# POWER_NEGATIVE.net
KiCad netlist of a schematic drawn in Altium Designer
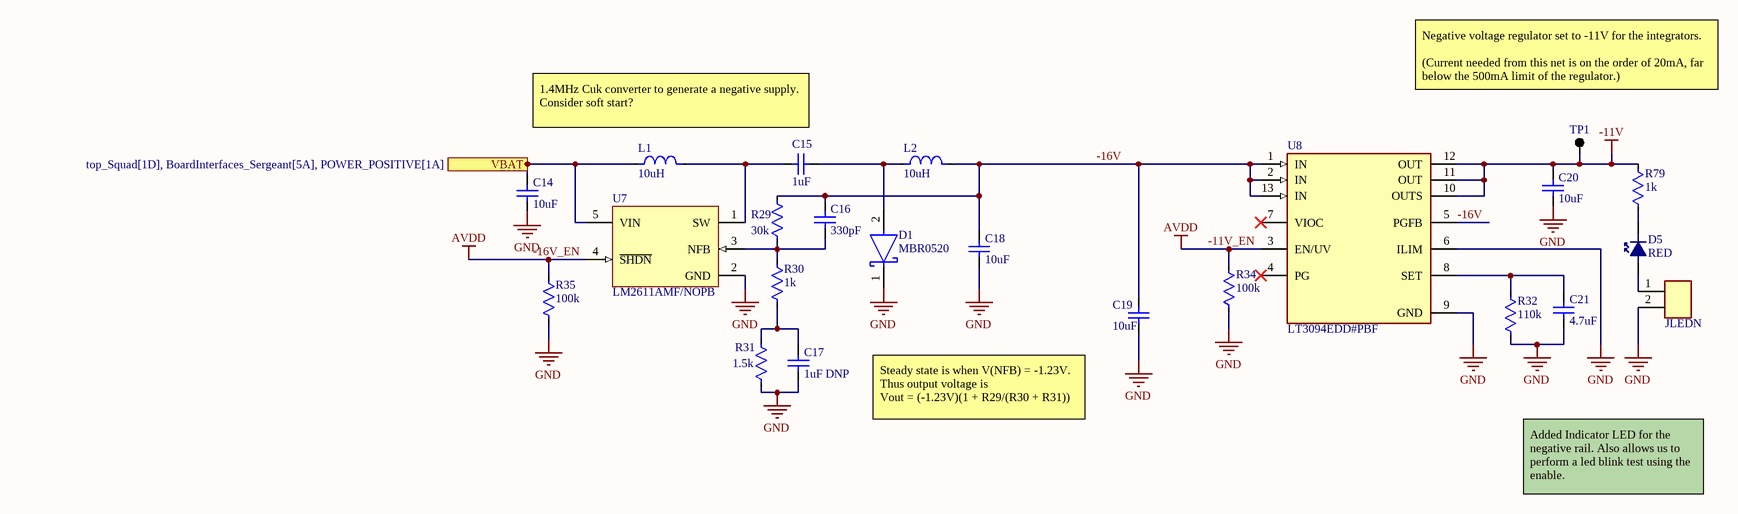
[diagram p0: POWER_NEGATIVE.SchDoc]

(export (version "E")
  (design (tool "Eeschema 10.0.6"))
  (components
    (comp (ref "C14")
      (value "10uF")
      (footprint "CAP 0805 IPC MID DENSITY")
      (description "Murata GRM21BR61E106KA73L - Cap Ceramic 10uF 10% 25V X5R 0805")
      (fields (field (name "MF") "Murata") (field (name "MP") "GRM21BR61E106KA73L"))
      (libsource (lib "ALTAIR_PD_Capacitors") (part "CAP"))
    )
    (comp (ref "C15")
      (value "1uF")
      (footprint "CAP 0603 IPC MID DENSITY")
      (description "Murata GRT188R61H105KE13D - Cap MLCC AEC-Q200 X5R 1uF 50V 0603")
      (fields (field (name "MF") "Murata") (field (name "MP") "GRT188R61H105KE13D"))
      (libsource (lib "ALTAIR_PD_Capacitors") (part "CAP"))
    )
    (comp (ref "C16")
      (value "330pF")
      (footprint "CAP 1206 NON-IPC KEMET NP0")
      (description "Kemet C1206C331J5GACTU - Cap Ceramic 330pF 50V 5% NP0 1206")
      (fields (field (name "MF") "Kemet") (field (name "MP") "C1206C331J5GACTU"))
      (libsource (lib "ALTAIR_PD_Capacitors") (part "CAP"))
    )
    (comp (ref "C17")
      (value "1uF DNP")
      (footprint "CAP 0603 IPC MID DENSITY")
      (description "Murata GRT188R61H105KE13D - Cap MLCC AEC-Q200 X5R 1uF 50V 0603")
      (fields (field (name "MF") "Murata") (field (name "MP") "GRT188R61H105KE13D"))
      (libsource (lib "ALTAIR_PD_Capacitors") (part "CAP"))
    )
    (comp (ref "C18")
      (value "10uF")
      (footprint "CAP 0805 IPC MID DENSITY")
      (description "Murata GRM21BR61E106KA73L - Cap Ceramic 10uF 10% 25V X5R 0805")
      (fields (field (name "MF") "Murata") (field (name "MP") "GRM21BR61E106KA73L"))
      (libsource (lib "ALTAIR_PD_Capacitors") (part "CAP"))
    )
    (comp (ref "C19")
      (value "10uF")
      (footprint "CAP 0805 IPC MID DENSITY")
      (description "Murata GRM21BR61E106KA73L - Cap Ceramic 10uF 10% 25V X5R 0805")
      (fields (field (name "MF") "Murata") (field (name "MP") "GRM21BR61E106KA73L"))
      (libsource (lib "ALTAIR_PD_Capacitors") (part "CAP"))
    )
    (comp (ref "C20")
      (value "10uF")
      (footprint "CAP 0805 IPC MID DENSITY")
      (description "Murata GRM21BR61E106KA73L - Cap Ceramic 10uF 10% 25V X5R 0805")
      (fields (field (name "MF") "Murata") (field (name "MP") "GRM21BR61E106KA73L"))
      (libsource (lib "ALTAIR_PD_Capacitors") (part "CAP"))
    )
    (comp (ref "C21")
      (value "4.7uF")
      (footprint "CAP 0805 NON-IPC KEMET X5R")
      (description "Kemet C0805C475K8PACTU - Cap Ceramic 4.7uF 10V X5R 0805")
      (fields (field (name "MF") "Kemet") (field (name "MP") "C0805C475K8PACTU"))
      (libsource (lib "ALTAIR_PD_Capacitors") (part "CAP"))
    )
    (comp (ref "D1")
      (value "MBR0520")
      (footprint "SOD-123 ONSEMI SMALL PADS")
      (description "DIODE SCHOTTKY 20V 500MA SOD123")
      (fields (field (name "MF") "onsemi") (field (name "MP") "MBR0520LT1G"))
      (libsource (lib "ALTAIR_PD_Diodes") (part "Schottky"))
    )
    (comp (ref "D5")
      (value "RED")
      (footprint "LED 0603 MID DENSITY")
      (description "LED RED CLEAR 0603 SMD")
      (fields (field (name "MF") "Wurth Electronics") (field (name "MP") "150060RS75000"))
      (libsource (lib "ALTAIR_PD_Diodes") (part "LED-blue"))
    )
    (comp (ref "JLEDN")
      (value "JLED")
      (footprint "JUMPER 2POS 1MM PITCH THT")
      (description "2x1 Header THT 1mm Pitch")
      (fields
        (field (name "MF") "GCT (GLOBAL CONNECTOR TECHNOLOGY)")
        (field (name "MP") "BC020-02-A-0200-0300-L-G")
      )
      (libsource (lib "ALTAIR_PD_Headers") (part "BC020-02-A-0200-0300-L-G"))
    )
    (comp (ref "L1")
      (value "10uH")
      (footprint "IND VLS3012CX-1 NONSTANDARD TDK")
      (description "TDK VLS3012CX-100M-1 - Inductor 10uH 20% 1.25A 0.324Ohm NonstandardPkg")
      (fields (field (name "TOLERANCE") "20%") (field (name "MF") "TDK Corporation"))
      (libsource (lib "ALTAIR_PD_Inductors") (part "IND"))
    )
    (comp (ref "L2")
      (value "10uH")
      (footprint "IND VLS3012CX-1 NONSTANDARD TDK")
      (description "TDK VLS3012CX-100M-1 - Inductor 10uH 20% 1.25A 0.324Ohm NonstandardPkg")
      (fields (field (name "TOLERANCE") "20%") (field (name "MF") "TDK Corporation"))
      (libsource (lib "ALTAIR_PD_Inductors") (part "IND"))
    )
    (comp (ref "R29")
      (value "30k")
      (footprint "RES 0805 IPC HIGH DENSITY")
      (description "Panasonic ERA-6AEB303V - Res 30kOhm 0.1% 1/8W 0805")
      (fields (field (name "MF") "Panasonic Electronic Components") (field (name "MP") "ERA-6AEB303V"))
      (libsource (lib "ALTAIR_PD_Resistors") (part "RES"))
    )
    (comp (ref "R30")
      (value "1k")
      (footprint "RES 0402 IPC LOW DENSITY YAGEO")
      (description "Yageo RC0402FR-071KL - Res 1kOhm 1% 1/16W 0402")
      (fields (field (name "MF") "YAGEO") (field (name "MP") "RC0402FR-071KL"))
      (libsource (lib "ALTAIR_PD_Resistors") (part "RES"))
    )
    (comp (ref "R31")
      (value "1.5k")
      (footprint "RES 1206 NON-IPC VISHAY")
      (description "Vishay TNPU12061K50BZEN00 - Res 1.5kOhm 0.1% 1/4W 1206")
      (fields (field (name "MF") "Vishay Dale") (field (name "MP") "TNPU12061K50BZEN00"))
      (libsource (lib "ALTAIR_PD_Resistors") (part "RES"))
    )
    (comp (ref "R32")
      (value "110k")
      (footprint "RES 0603 IPC MID DENSITY")
      (description "Panasonic ERA-3AEB114V - Res 110k 0.1% 1/10W SMD 0603")
      (fields (field (name "MF") "Panasonic Electronic Components") (field (name "MP") "ERA-3AEB114V"))
      (libsource (lib "ALTAIR_PD_Resistors") (part "RES"))
    )
    (comp (ref "R34")
      (value "100k")
      (footprint "RES 0603 IPC MID DENSITY")
      (description "Panasonic ERJ-3GEYJ104V - Res 100k 5% 1/10W SMD 0603")
      (fields (field (name "MF") "Panasonic Electronic Components") (field (name "MP") "ERJ-3GEYJ104V"))
      (libsource (lib "ALTAIR_PD_Resistors") (part "RES"))
    )
    (comp (ref "R35")
      (value "100k")
      (footprint "RES 0603 IPC MID DENSITY")
      (description "Panasonic ERJ-3GEYJ104V - Res 100k 5% 1/10W SMD 0603")
      (fields (field (name "MF") "Panasonic Electronic Components") (field (name "MP") "ERJ-3GEYJ104V"))
      (libsource (lib "ALTAIR_PD_Resistors") (part "RES"))
    )
    (comp (ref "R79")
      (value "1k")
      (footprint "RES 0603 IPC MID DENSITY")
      (description "Panasonic ERJ-U03F1001V - Res SMD 1 kOhm 1% 1/10W 0603")
      (fields (field (name "MF") "Panasonic Electronic Components") (field (name "MP") "ERJ-U03F1001V"))
      (libsource (lib "ALTAIR_PD_Resistors") (part "RES"))
    )
    (comp (ref "TP1")
      (value "Testpoint")
      (footprint "TESTPOINT THT")
      (libsource (lib "ALTAIR_PD_Testpoint") (part "Testpoint"))
    )
    (comp (ref "U7")
      (value "LM2611AMF/NOPB")
      (footprint "SOT23-5 MID DENSITY")
      (description "1.4MHz Cuk Converter, 5-pin SOT-23, Pb-Free")
      (fields (field (name "MF") "Texas Instruments"))
      (libsource (lib "ALTAIR_PD_Converters") (part "LM2611AMF"))
    )
    (comp (ref "U8")
      (value "LT3094EDD#PBF")
      (footprint "12DFN 3x3MM EP IPC MID DENSITY")
      (description "-20V 500mA Ultralow Noise Ultrahigh PSRR Adjustable Negative Linear Regulator 12DFN")
      (fields (field (name "MF") "Analog Devices"))
      (libsource (lib "ALTAIR_PD_Regulators") (part "LT3094EDD#PBF"))
    )
  )
  (nets
    (net (code "1") (name "-11V") (class "Default")
      (node (ref "C20") (pin "1") (pinfunction "1_1") (pintype "passive"))
      (node (ref "R79") (pin "2") (pinfunction "2_2") (pintype "passive"))
      (node (ref "TP1") (pin "1") (pinfunction "1_1") (pintype "passive"))
      (node (ref "U8") (pin "10") (pinfunction "OUTS_10") (pintype "power_in"))
      (node (ref "U8") (pin "11") (pinfunction "OUT_11") (pintype "power_in"))
      (node (ref "U8") (pin "12") (pinfunction "OUT_12") (pintype "power_in"))
    )
    (net (code "2") (name "/-16V") (class "Default")
      (node (ref "C16") (pin "1") (pinfunction "1_1") (pintype "passive"))
      (node (ref "C18") (pin "1") (pinfunction "1_1") (pintype "passive"))
      (node (ref "C19") (pin "1") (pinfunction "1_1") (pintype "passive"))
      (node (ref "L2") (pin "2") (pinfunction "2_2") (pintype "passive"))
      (node (ref "R29") (pin "2") (pinfunction "2_2") (pintype "passive"))
      (node (ref "U8") (pin "1") (pinfunction "IN_1") (pintype "input"))
      (node (ref "U8") (pin "13") (pinfunction "IN_13") (pintype "input"))
      (node (ref "U8") (pin "2") (pinfunction "IN_2") (pintype "input"))
      (node (ref "U8") (pin "5") (pinfunction "PGFB_5") (pintype "passive"))
    )
    (net (code "3") (name "/VBAT") (class "Default")
      (node (ref "C14") (pin "2") (pinfunction "2_2") (pintype "passive"))
      (node (ref "L1") (pin "1") (pinfunction "1_1") (pintype "passive"))
      (node (ref "U7") (pin "5") (pinfunction "VIN_5") (pintype "power_in"))
    )
    (net (code "4") (name "AVDD") (class "Default")
      (node (ref "R34") (pin "1") (pinfunction "1_1") (pintype "passive"))
      (node (ref "R35") (pin "1") (pinfunction "1_1") (pintype "passive"))
      (node (ref "U7") (pin "4") (pinfunction "~{SHDN}_4") (pintype "input"))
      (node (ref "U8") (pin "3") (pinfunction "EN/UV_3") (pintype "passive"))
    )
    (net (code "5") (name "GND") (class "Default")
      (node (ref "C14") (pin "1") (pinfunction "1_1") (pintype "passive"))
      (node (ref "C17") (pin "2") (pinfunction "2_2") (pintype "passive"))
      (node (ref "C18") (pin "2") (pinfunction "2_2") (pintype "passive"))
      (node (ref "C19") (pin "2") (pinfunction "2_2") (pintype "passive"))
      (node (ref "C20") (pin "2") (pinfunction "2_2") (pintype "passive"))
      (node (ref "C21") (pin "2") (pinfunction "2_2") (pintype "passive"))
      (node (ref "D1") (pin "1") (pinfunction "C_1") (pintype "passive"))
      (node (ref "JLEDN") (pin "2") (pinfunction "2_2") (pintype "passive"))
      (node (ref "R31") (pin "1") (pinfunction "1_1") (pintype "passive"))
      (node (ref "R32") (pin "2") (pinfunction "2_2") (pintype "passive"))
      (node (ref "R34") (pin "2") (pinfunction "2_2") (pintype "passive"))
      (node (ref "R35") (pin "2") (pinfunction "2_2") (pintype "passive"))
      (node (ref "U7") (pin "2") (pinfunction "GND_2") (pintype "power_in"))
      (node (ref "U8") (pin "6") (pinfunction "ILIM_6") (pintype "passive"))
      (node (ref "U8") (pin "9") (pinfunction "GND_9") (pintype "power_in"))
    )
    (net (code "6") (name "Net-(C17-Pad1)") (class "Default")
      (node (ref "C17") (pin "1") (pinfunction "1_1") (pintype "passive"))
      (node (ref "R30") (pin "1") (pinfunction "1_1") (pintype "passive"))
      (node (ref "R31") (pin "2") (pinfunction "2_2") (pintype "passive"))
    )
    (net (code "7") (name "Net-(D1-A)") (class "Default")
      (node (ref "C15") (pin "2") (pinfunction "2_2") (pintype "passive"))
      (node (ref "D1") (pin "2") (pinfunction "A_2") (pintype "passive"))
      (node (ref "L2") (pin "1") (pinfunction "1_1") (pintype "passive"))
    )
    (net (code "8") (name "Net-(D5-Pad1)") (class "Default")
      (node (ref "D5") (pin "1") (pinfunction "1_1") (pintype "passive"))
      (node (ref "R79") (pin "1") (pinfunction "1_1") (pintype "passive"))
    )
    (net (code "9") (name "Net-(D5-Pad2)") (class "Default")
      (node (ref "D5") (pin "2") (pinfunction "2_2") (pintype "passive"))
      (node (ref "JLEDN") (pin "1") (pinfunction "1_1") (pintype "passive"))
    )
    (net (code "10") (name "Net-(U7-NFB)") (class "Default")
      (node (ref "C16") (pin "2") (pinfunction "2_2") (pintype "passive"))
      (node (ref "R29") (pin "1") (pinfunction "1_1") (pintype "passive"))
      (node (ref "R30") (pin "2") (pinfunction "2_2") (pintype "passive"))
      (node (ref "U7") (pin "3") (pinfunction "NFB_3") (pintype "input"))
    )
    (net (code "11") (name "Net-(U7-SW)") (class "Default")
      (node (ref "C15") (pin "1") (pinfunction "1_1") (pintype "passive"))
      (node (ref "L1") (pin "2") (pinfunction "2_2") (pintype "passive"))
      (node (ref "U7") (pin "1") (pinfunction "SW_1") (pintype "power_in"))
    )
    (net (code "12") (name "Net-(U8-SET)") (class "Default")
      (node (ref "C21") (pin "1") (pinfunction "1_1") (pintype "passive"))
      (node (ref "R32") (pin "1") (pinfunction "1_1") (pintype "passive"))
      (node (ref "U8") (pin "8") (pinfunction "SET_8") (pintype "passive"))
    )
    (net (code "13") (name "unconnected-(U8-PG-Pad4)") (class "Default")
      (node (ref "U8") (pin "4") (pinfunction "PG_4") (pintype "passive+no_connect"))
    )
    (net (code "14") (name "unconnected-(U8-VIOC-Pad7)") (class "Default")
      (node (ref "U8") (pin "7") (pinfunction "VIOC_7") (pintype "passive+no_connect"))
    )
  )
)
